# SD_USB_FMU3_REV_C.net
KiCad netlist of a schematic drawn in Altium Designer
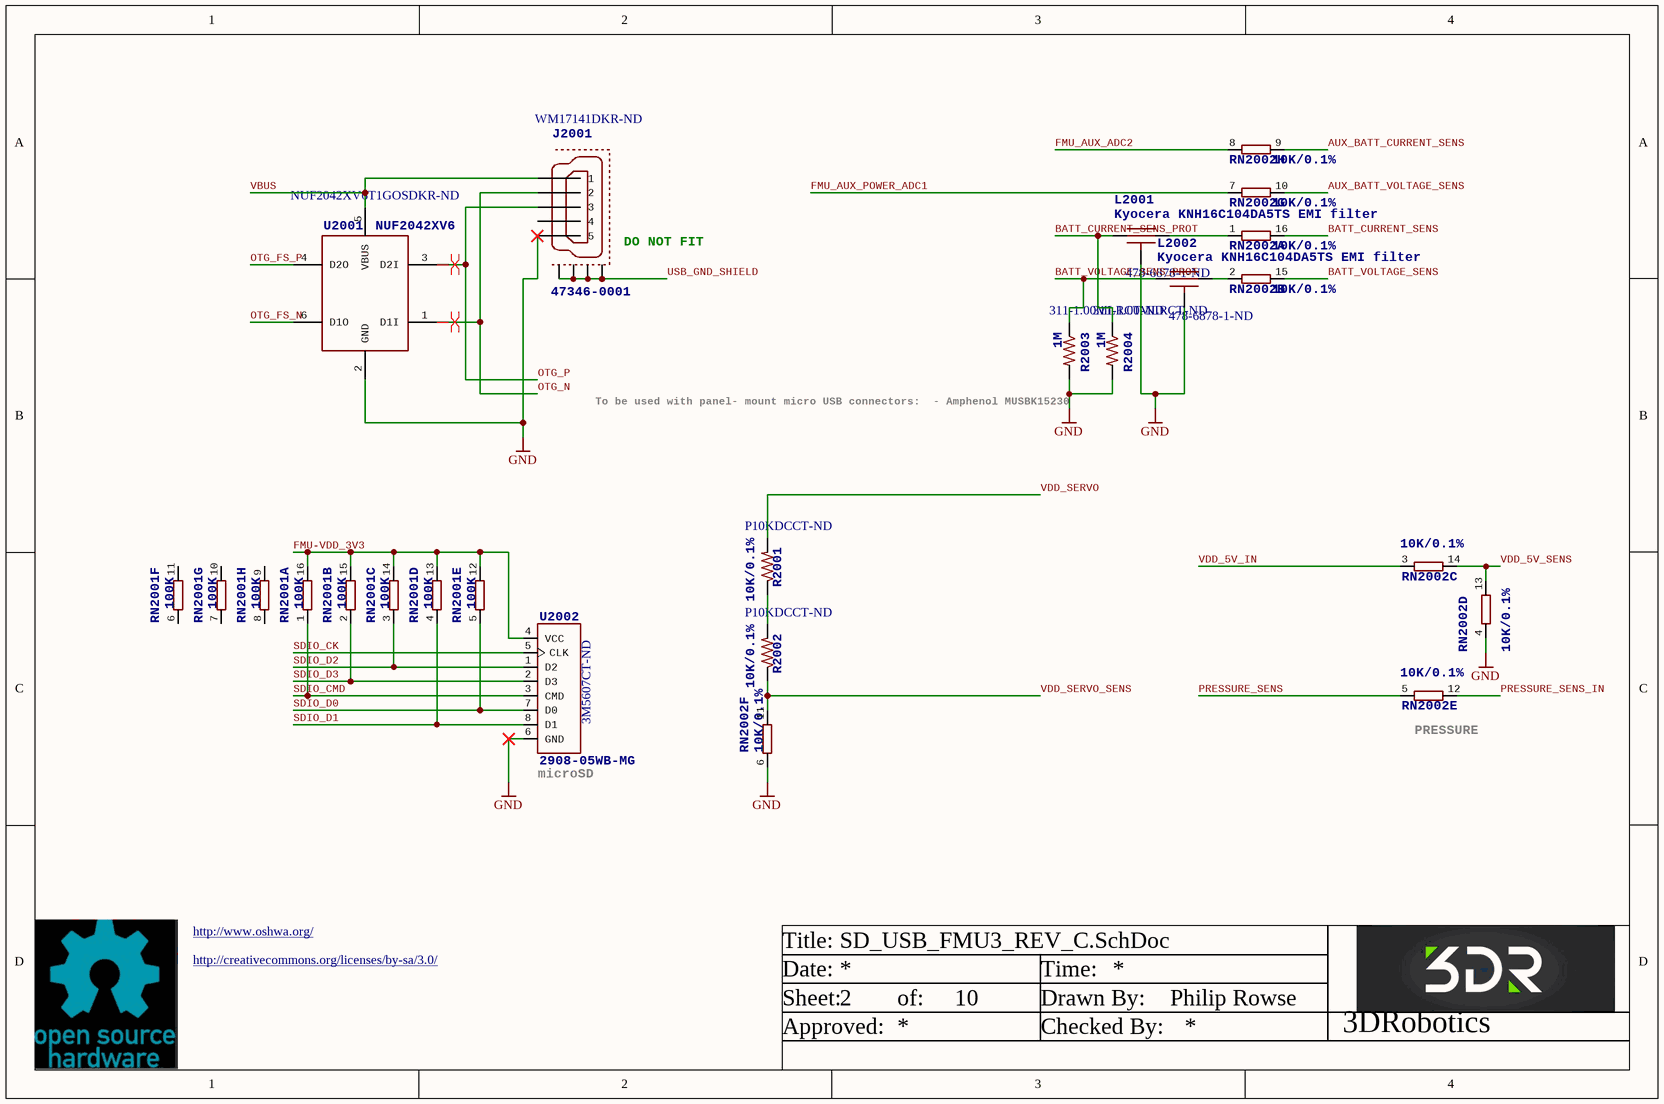
[diagram p0: SD_USB_FMU3_REV_C.SchDoc]

(export (version "E")
  (design (tool "Eeschema 10.0.6"))
  (components
    (comp (ref "J2001")
      (value "47346-0001")
      (footprint "MOLEX-47346-0001")
      (description "MICRO USB B, BOTTOM MOUNT")
      (fields
        (field (name "SUPPLIER PART NUMBER 1") "WM17141DKR-ND")
        (field (name "3DR_PARTNO") "ECM0486")
        (field (name "PARTNO") "0473460001")
      )
      (libsource (lib "pixhawk2") (part "MOLEX-47346-0001"))
    )
    (comp (ref "L2001")
      (value "Kyocera KNH16C104DA5TS EMI filter")
      (footprint "KYOCERA-KNH16-DA")
      (description "FILTER CAP 0.1UF 2A 25V 0603")
      (fields
        (field (name "SUPPLIER PART NUMBER 1") "478-6878-1-ND")
        (field (name "3DR_PARTNO") "ECM0719")
        (field (name "PARTNO") "KNH16C104DA5TS")
      )
      (libsource (lib "pixhawk2") (part "KNH16C104DA5TS"))
    )
    (comp (ref "L2002")
      (value "Kyocera KNH16C104DA5TS EMI filter")
      (footprint "KYOCERA-KNH16-DA")
      (description "FILTER CAP 0.1UF 2A 25V 0603")
      (fields
        (field (name "SUPPLIER PART NUMBER 1") "478-6878-1-ND")
        (field (name "3DR_PARTNO") "ECM0719")
        (field (name "PARTNO") "KNH16C104DA5TS")
      )
      (libsource (lib "pixhawk2") (part "KNH16C104DA5TS"))
    )
    (comp (ref "R2001")
      (value "10K/0.1%")
      (footprint "0402-RES")
      (description "RES 10K OHM 1/16W .1% 0402 SMD")
      (fields
        (field (name "SUPPLIER PART NUMBER 1") "P10KDCCT-ND")
        (field (name "3DR_PARTNO") "ECM0810")
        (field (name "PARTNO") "ERA-2AEB103X")
      )
      (libsource (lib "pixhawk2") (part "RESISTOR0402-RES"))
    )
    (comp (ref "R2002")
      (value "10K/0.1%")
      (footprint "0402-RES")
      (description "RES 10K OHM 1/16W .1% 0402 SMD")
      (fields
        (field (name "SUPPLIER PART NUMBER 1") "P10KDCCT-ND")
        (field (name "3DR_PARTNO") "ECM0810")
        (field (name "PARTNO") "ERA-2AEB103X")
      )
      (libsource (lib "pixhawk2") (part "RESISTOR0402-RES"))
    )
    (comp (ref "R2003")
      (value "1M")
      (footprint "0402-RES")
      (description "RES 1M OHM 1/16W 1% 0402 SMD")
      (fields
        (field (name "PARTNO") "RC0402FR-071ML")
        (field (name "SUPPLIER PART NUMBER 1") "311-1.00MLRCT-ND")
        (field (name "3DR_PARTNO") "ECM0806")
      )
      (libsource (lib "pixhawk2") (part "RESISTOR0402-RES"))
    )
    (comp (ref "R2004")
      (value "1M")
      (footprint "0402-RES")
      (description "RES 1M OHM 1/16W 1% 0402 SMD")
      (fields
        (field (name "PARTNO") "RC0402FR-071ML")
        (field (name "SUPPLIER PART NUMBER 1") "311-1.00MLRCT-ND")
        (field (name "3DR_PARTNO") "ECM0806")
      )
      (libsource (lib "pixhawk2") (part "RESISTOR0402-RES"))
    )
    (comp (ref "RN2001")
      (value "100K")
      (footprint "EXB2HV")
      (description "RES ARRAY 100K OHM 8 RES 1506")
      (fields (field (name "PARTNO") "EXB-2HV104JV") (field (name "3DR_PARTNO") "ECM0101"))
      (libsource (lib "pixhawk2") (part "8R-NEXB2HV-100K"))
    )
    (comp (ref "RN2002")
      (value "10K/0.1%")
      (footprint "EXB2HV")
      (description "RES ARRAY 10K OHM 8 RES 1506")
      (fields (field (name "PARTNO") "EXB-2HV103JV") (field (name "3DR_PARTNO") "ECM0546"))
      (libsource (lib "pixhawk2") (part "8R-NEXB2HV-10K"))
    )
    (comp (ref "U2001")
      (value "NUF2042XV6")
      (footprint "SOT563-6")
      (description "IC FILTER USB ESD PROTECT SOT363")
      (fields
        (field (name "PARTNO") "NUF2042XV6T1G")
        (field (name "SUPPLIER PART NUMBER 1") "NUF2042XV6T1GOSDKR-ND")
        (field (name "3DR_PARTNO") "ECM0836")
      )
      (libsource (lib "pixhawk2") (part "NUF2042XV6"))
    )
    (comp (ref "U2002")
      (value "2908-05WB-MG")
      (footprint "MICROSD")
      (description "CONN MICRO SD CARD PUSH-PUSH R/A")
      (fields (field (name "SUPPLIER PART NUMBER 1") "3M5607CT-ND") (field (name "3DR_PARTNO") "ECM0485"))
      (libsource (lib "baseboard") (part "MICROSDSDI"))
    )
  )
  (nets
    (net (code "1") (name "/AUX_BATT_CURRENT_SENS") (class "Default")
      (node (ref "RN2002") (pin "9") (pinfunction "2_9") (pintype "passive"))
    )
    (net (code "2") (name "/AUX_BATT_VOLTAGE_SENS") (class "Default")
      (node (ref "RN2002") (pin "10") (pinfunction "2_10") (pintype "passive"))
    )
    (net (code "3") (name "/BATT_CURRENT_SENS") (class "Default")
      (node (ref "RN2002") (pin "16") (pinfunction "2_16") (pintype "passive"))
    )
    (net (code "4") (name "/BATT_CURRENT_SENS_PROT") (class "Default")
      (node (ref "L2001") (pin "P$1") (pinfunction "P$1_P$1") (pintype "passive"))
      (node (ref "R2004") (pin "P$1") (pinfunction "1_P$1") (pintype "passive"))
    )
    (net (code "5") (name "/BATT_VOLTAGE_SENS") (class "Default")
      (node (ref "RN2002") (pin "15") (pinfunction "2_15") (pintype "passive"))
    )
    (net (code "6") (name "/BATT_VOLTAGE_SENS_PROT") (class "Default")
      (node (ref "L2002") (pin "P$1") (pinfunction "P$1_P$1") (pintype "passive"))
      (node (ref "R2003") (pin "P$1") (pinfunction "1_P$1") (pintype "passive"))
    )
    (net (code "7") (name "/FMU-VDD_3V3") (class "Default")
      (node (ref "RN2001") (pin "12") (pinfunction "2_12") (pintype "passive"))
      (node (ref "RN2001") (pin "13") (pinfunction "2_13") (pintype "passive"))
      (node (ref "RN2001") (pin "14") (pinfunction "2_14") (pintype "passive"))
      (node (ref "RN2001") (pin "15") (pinfunction "2_15") (pintype "passive"))
      (node (ref "RN2001") (pin "16") (pinfunction "2_16") (pintype "passive"))
      (node (ref "U2002") (pin "4") (pinfunction "VCC_4") (pintype "passive"))
    )
    (net (code "8") (name "/FMU_AUX_ADC2") (class "Default")
      (node (ref "RN2002") (pin "8") (pinfunction "1_8") (pintype "passive"))
    )
    (net (code "9") (name "/FMU_AUX_POWER_ADC1") (class "Default")
      (node (ref "RN2002") (pin "7") (pinfunction "1_7") (pintype "passive"))
    )
    (net (code "10") (name "/OTG_FS_N") (class "Default")
      (node (ref "U2001") (pin "6") (pinfunction "D1O_6") (pintype "passive"))
    )
    (net (code "11") (name "/OTG_FS_P") (class "Default")
      (node (ref "U2001") (pin "4") (pinfunction "D2O_4") (pintype "passive"))
    )
    (net (code "12") (name "/OTG_N") (class "Default")
      (node (ref "J2001") (pin "D-") (pinfunction "2_D-") (pintype "passive"))
      (node (ref "U2001") (pin "1") (pinfunction "D1I_1") (pintype "passive"))
    )
    (net (code "13") (name "/OTG_P") (class "Default")
      (node (ref "J2001") (pin "D+") (pinfunction "3_D+") (pintype "passive"))
      (node (ref "U2001") (pin "3") (pinfunction "D2I_3") (pintype "passive"))
    )
    (net (code "14") (name "/PRESSURE_SENS") (class "Default")
      (node (ref "RN2002") (pin "5") (pinfunction "1_5") (pintype "passive"))
    )
    (net (code "15") (name "/PRESSURE_SENS_IN") (class "Default")
      (node (ref "RN2002") (pin "12") (pinfunction "2_12") (pintype "passive"))
    )
    (net (code "16") (name "/SDIO_CK") (class "Default")
      (node (ref "U2002") (pin "5") (pinfunction "CLK_5") (pintype "passive"))
    )
    (net (code "17") (name "/SDIO_CMD") (class "Default")
      (node (ref "RN2001") (pin "1") (pinfunction "1_1") (pintype "passive"))
      (node (ref "U2002") (pin "3") (pinfunction "CMD_3") (pintype "passive"))
    )
    (net (code "18") (name "/SDIO_D0") (class "Default")
      (node (ref "RN2001") (pin "5") (pinfunction "1_5") (pintype "passive"))
      (node (ref "U2002") (pin "7") (pinfunction "D0_7") (pintype "passive"))
    )
    (net (code "19") (name "/SDIO_D1") (class "Default")
      (node (ref "RN2001") (pin "4") (pinfunction "1_4") (pintype "passive"))
      (node (ref "U2002") (pin "8") (pinfunction "D1_8") (pintype "passive"))
    )
    (net (code "20") (name "/SDIO_D2") (class "Default")
      (node (ref "RN2001") (pin "3") (pinfunction "1_3") (pintype "passive"))
      (node (ref "U2002") (pin "1") (pinfunction "D2_1") (pintype "passive"))
    )
    (net (code "21") (name "/SDIO_D3") (class "Default")
      (node (ref "RN2001") (pin "2") (pinfunction "1_2") (pintype "passive"))
      (node (ref "U2002") (pin "2") (pinfunction "D3_2") (pintype "passive"))
    )
    (net (code "22") (name "/USB_GND_SHIELD") (class "Default")
      (node (ref "J2001") (pin "GND1") (pinfunction "GND1_GND1") (pintype "passive"))
      (node (ref "J2001") (pin "GND2") (pinfunction "GND2_GND2") (pintype "passive"))
      (node (ref "J2001") (pin "GND3") (pinfunction "GND3_GND3") (pintype "passive"))
      (node (ref "J2001") (pin "GND4") (pinfunction "GND4_GND4") (pintype "passive"))
    )
    (net (code "23") (name "/VBUS") (class "Default")
      (node (ref "J2001") (pin "VBUS") (pinfunction "1_VBUS") (pintype "open_emitter"))
      (node (ref "U2001") (pin "5") (pinfunction "VBUS_5") (pintype "passive"))
    )
    (net (code "24") (name "/VDD_5V_IN") (class "Default")
      (node (ref "RN2002") (pin "3") (pinfunction "1_3") (pintype "passive"))
    )
    (net (code "25") (name "/VDD_5V_SENS") (class "Default")
      (node (ref "RN2002") (pin "13") (pinfunction "2_13") (pintype "passive"))
      (node (ref "RN2002") (pin "14") (pinfunction "2_14") (pintype "passive"))
    )
    (net (code "26") (name "/VDD_SERVO") (class "Default")
      (node (ref "R2001") (pin "P$2") (pinfunction "2_P$2") (pintype "passive"))
    )
    (net (code "27") (name "/VDD_SERVO_SENS") (class "Default")
      (node (ref "R2002") (pin "P$1") (pinfunction "1_P$1") (pintype "passive"))
      (node (ref "RN2002") (pin "11") (pinfunction "2_11") (pintype "passive"))
    )
    (net (code "28") (name "GND") (class "Default")
      (node (ref "J2001") (pin "GND") (pinfunction "5_GND") (pintype "open_emitter"))
      (node (ref "L2001") (pin "GND") (pinfunction "GND_GND") (pintype "passive"))
      (node (ref "L2002") (pin "GND") (pinfunction "GND_GND") (pintype "passive"))
      (node (ref "R2003") (pin "P$2") (pinfunction "2_P$2") (pintype "passive"))
      (node (ref "R2004") (pin "P$2") (pinfunction "2_P$2") (pintype "passive"))
      (node (ref "RN2002") (pin "4") (pinfunction "1_4") (pintype "passive"))
      (node (ref "RN2002") (pin "6") (pinfunction "1_6") (pintype "passive"))
      (node (ref "U2001") (pin "2") (pinfunction "GND_2") (pintype "passive"))
      (node (ref "U2002") (pin "6") (pinfunction "GND_6") (pintype "open_emitter"))
    )
    (net (code "29") (name "Net-(L2001-PadP$2)") (class "Default")
      (node (ref "L2001") (pin "P$2") (pinfunction "P$2_P$2") (pintype "passive"))
      (node (ref "RN2002") (pin "1") (pinfunction "1_1") (pintype "passive"))
    )
    (net (code "30") (name "Net-(R2001-1)") (class "Default")
      (node (ref "R2001") (pin "P$1") (pinfunction "1_P$1") (pintype "passive"))
      (node (ref "R2002") (pin "P$2") (pinfunction "2_P$2") (pintype "passive"))
    )
    (net (code "31") (name "Net-(RN2002B-1)") (class "Default")
      (node (ref "L2002") (pin "P$2") (pinfunction "P$2_P$2") (pintype "passive"))
      (node (ref "RN2002") (pin "2") (pinfunction "1_2") (pintype "passive"))
    )
    (net (code "32") (name "unconnected-(J2001-4-PadID)") (class "Default")
      (node (ref "J2001") (pin "ID") (pinfunction "4_ID") (pintype "passive"))
    )
    (net (code "33") (name "unconnected-(RN2001F-1-Pad6)") (class "Default")
      (node (ref "RN2001") (pin "6") (pinfunction "1_6") (pintype "passive"))
    )
    (net (code "34") (name "unconnected-(RN2001F-2-Pad11)") (class "Default")
      (node (ref "RN2001") (pin "11") (pinfunction "2_11") (pintype "passive"))
    )
    (net (code "35") (name "unconnected-(RN2001G-1-Pad7)") (class "Default")
      (node (ref "RN2001") (pin "7") (pinfunction "1_7") (pintype "passive"))
    )
    (net (code "36") (name "unconnected-(RN2001G-2-Pad10)") (class "Default")
      (node (ref "RN2001") (pin "10") (pinfunction "2_10") (pintype "passive"))
    )
    (net (code "37") (name "unconnected-(RN2001H-1-Pad8)") (class "Default")
      (node (ref "RN2001") (pin "8") (pinfunction "1_8") (pintype "passive"))
    )
    (net (code "38") (name "unconnected-(RN2001H-2-Pad9)") (class "Default")
      (node (ref "RN2001") (pin "9") (pinfunction "2_9") (pintype "passive"))
    )
  )
)
